# 1_POWER.net
KiCad netlist of a schematic drawn in Altium Designer
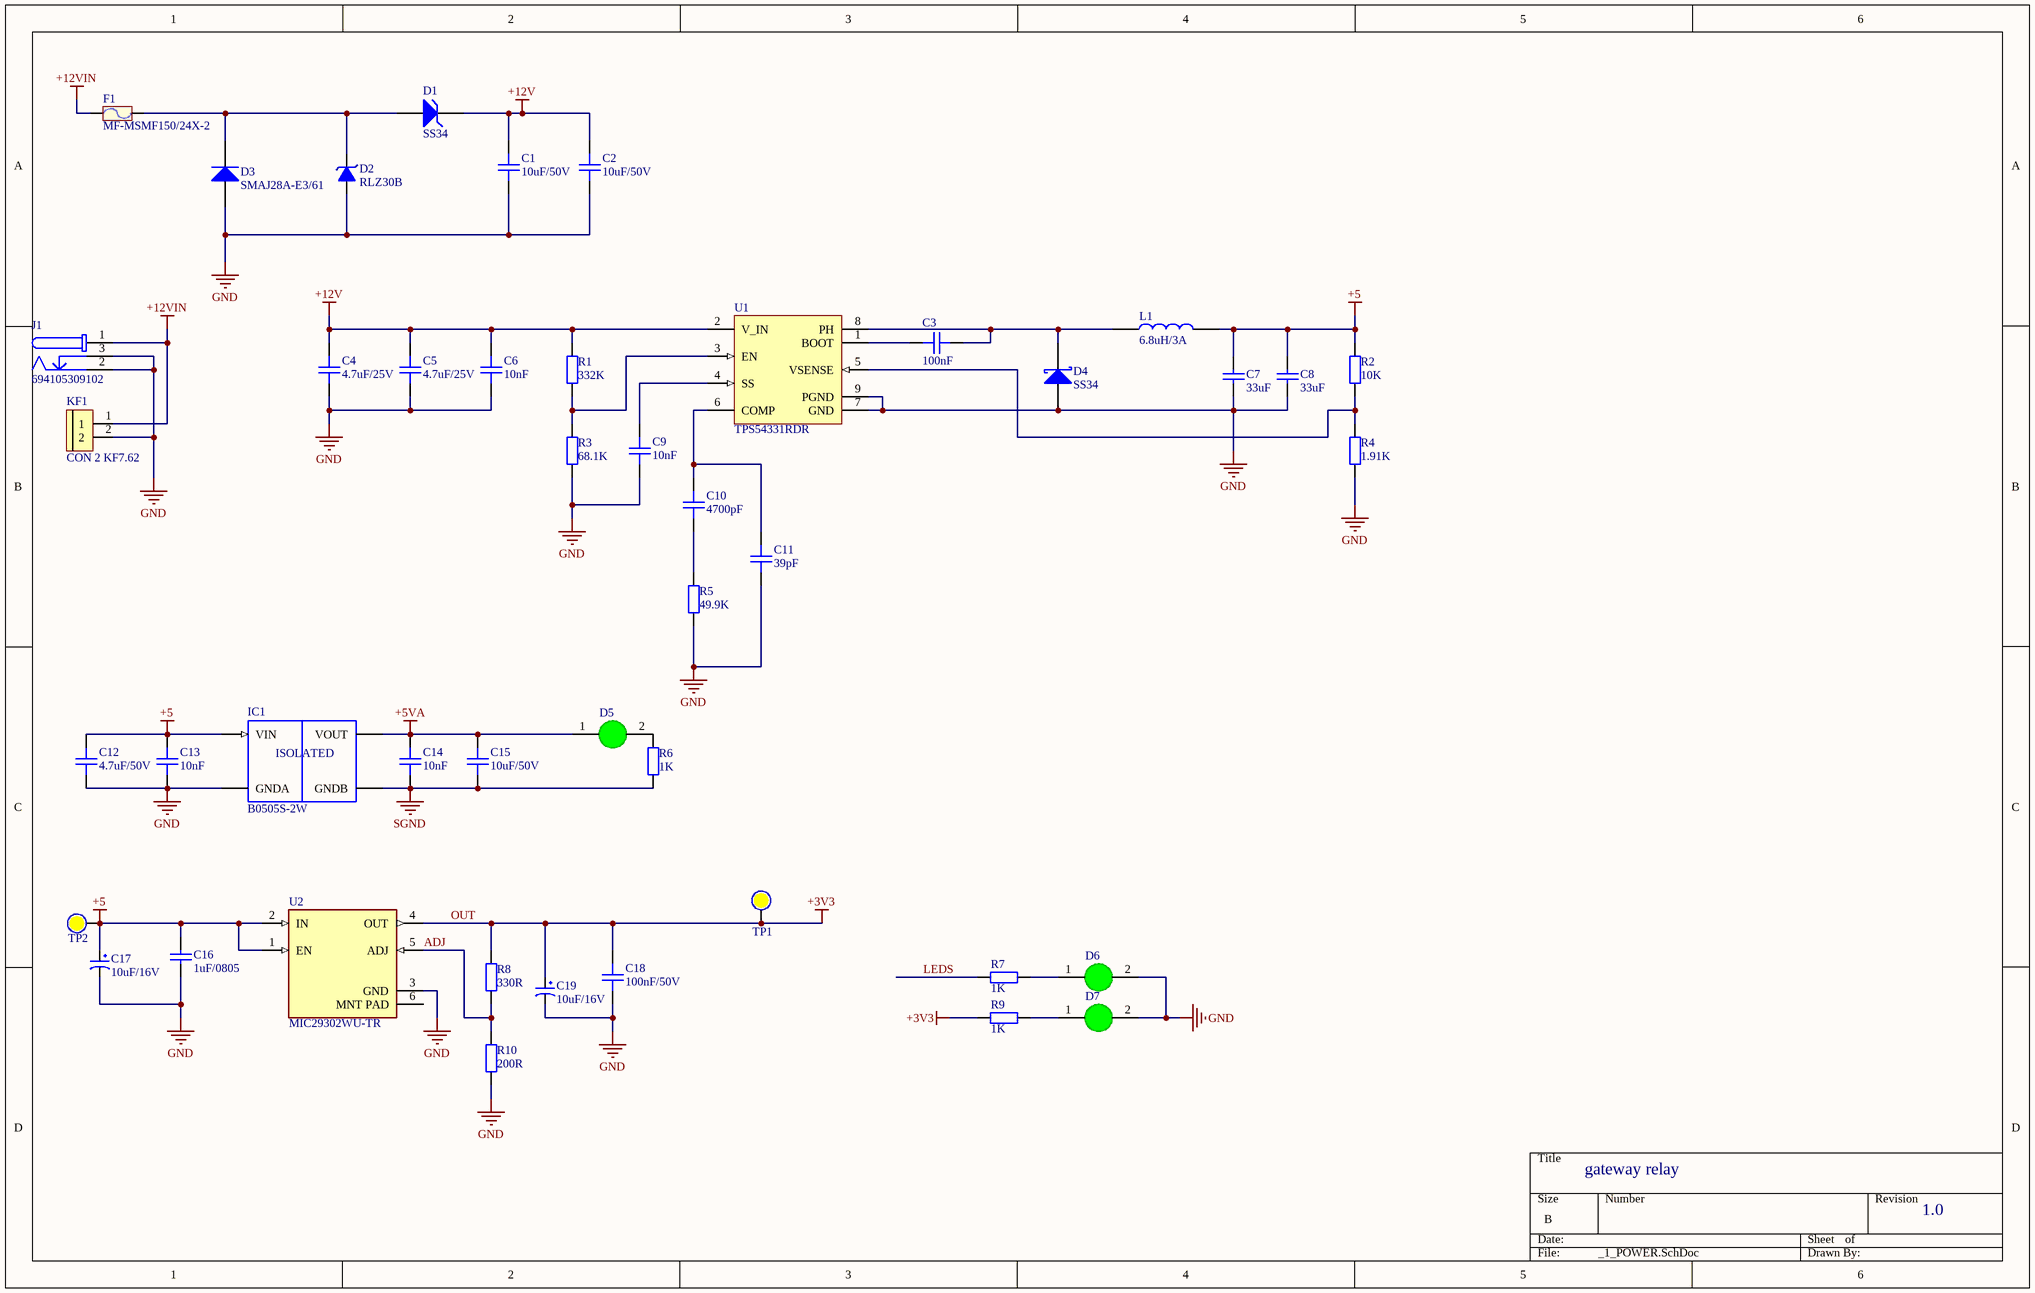
[diagram p0: _1_POWER.SchDoc]

(export (version "E")
  (design (tool "Eeschema 10.0.6"))
  (components
    (comp (ref "C1")
      (value "10uF/50V")
      (footprint "1210")
      (description "CAP CER 10uF/50V 1210")
      (fields (field (name "MANUFACTURER") "Yageo") (field (name "PART NUMBER") "C1210"))
      (libsource (lib "COMPONENT_INS") (part "CAP_CER_1210_10uF"))
    )
    (comp (ref "C2")
      (value "10uF/50V")
      (footprint "1210")
      (description "CAP CER 10uF/50V 1210")
      (fields (field (name "MANUFACTURER") "Yageo") (field (name "PART NUMBER") "C1210"))
      (libsource (lib "COMPONENT_INS") (part "CAP_CER_1210_10uF"))
    )
    (comp (ref "C3")
      (value "100nF")
      (footprint "CAPC-0603 (1608)")
      (description "CAP CER 0.22UF 50V Y5V 0603")
      (fields (field (name "MPN") "CC0603ZRY5V9BB224"))
      (libsource (lib "BYTECH_HW_LIB_2019") (part "CC0603ZRY5V9BB224"))
    )
    (comp (ref "C4")
      (value "4.7uF/25V")
      (footprint "CAPC-1210 (3225)")
      (description "CAP CER 1UF 50V X7R 1210")
      (fields (field (name "MPN") "CC1210KKX7R9BB105") (field (name "MFR") "Yageo"))
      (libsource (lib "BYTECH_HW_LIB_2019") (part "CC1210KKX7R9BB105"))
    )
    (comp (ref "C5")
      (value "4.7uF/25V")
      (footprint "CAPC-1210 (3225)")
      (description "CAP CER 1UF 50V X7R 1210")
      (fields (field (name "MPN") "CC1210KKX7R9BB105") (field (name "MFR") "Yageo"))
      (libsource (lib "BYTECH_HW_LIB_2019") (part "CC1210KKX7R9BB105"))
    )
    (comp (ref "C6")
      (value "10nF")
      (footprint "CAPC-0603 (1608)")
      (description "CAP CER 10nF 16V 10% X7R 0603")
      (fields (field (name "MPN") "CC0603KRX7R7BB103"))
      (libsource (lib "BYTECH_HW_LIB_2019") (part "CC0603KRX7R7BB103"))
    )
    (comp (ref "C7")
      (value "33uF")
      (footprint "tu 1206")
      (description "Dán")
      (libsource (lib "Altium_Lib_by_KhueNguyenCreator") (part "Tu 1206 100pF 50V 5%"))
    )
    (comp (ref "C8")
      (value "33uF")
      (footprint "tu 1206")
      (description "Dán")
      (libsource (lib "Altium_Lib_by_KhueNguyenCreator") (part "Tu 1206 100pF 50V 5%"))
    )
    (comp (ref "C9")
      (value "10nF")
      (footprint "CAPC-0603 (1608)")
      (description "CAP CER 10nF 16V 10% X7R 0603")
      (fields (field (name "MPN") "CC0603KRX7R7BB103"))
      (libsource (lib "BYTECH_HW_LIB_2019") (part "CC0603KRX7R7BB103"))
    )
    (comp (ref "C10")
      (value "4700pF")
      (footprint "CAPC-0603 (1608)")
      (description "CAP CER 8200PF 50V X7R 0603")
      (fields (field (name "MPN") "CC0603KRX7R9BB822") (field (name "MFR") "Yageo"))
      (libsource (lib "BYTECH_HW_LIB_2019") (part "CC0603KRX7R9BB822"))
    )
    (comp (ref "C11")
      (value "39pF")
      (footprint "CAPC-0603 (1608)")
      (description "CAP CER 56PF 50V 5% COG/NPO 0603")
      (fields (field (name "MPN") "CC0603JRNPO9BN560"))
      (libsource (lib "BYTECH_HW_LIB_2019") (part "CC0603JRNPO9BN560"))
    )
    (comp (ref "C12")
      (value "4.7uF/50V")
      (footprint "CAPC-0805 (2012)")
      (description "CAP CER 4.7uF -20% +80% 10V Y5V 0805")
      (fields (field (name "MPN") "CC0805ZRY5V6BB475"))
      (libsource (lib "BYTECH_HW_LIB_2019") (part "CC0805ZRY5V6BB475"))
    )
    (comp (ref "C13")
      (value "10nF")
      (footprint "CAPC-0603 (1608)")
      (description "CAP CER 10nF 16V 10% X7R 0603")
      (fields (field (name "MPN") "CC0603KRX7R7BB103"))
      (libsource (lib "BYTECH_HW_LIB_2019") (part "CC0603KRX7R7BB103"))
    )
    (comp (ref "C14")
      (value "10nF")
      (footprint "CAPC-0603 (1608)")
      (description "CAP CER 10nF 16V 10% X7R 0603")
      (fields (field (name "MPN") "CC0603KRX7R7BB103"))
      (libsource (lib "BYTECH_HW_LIB_2019") (part "CC0603KRX7R7BB103"))
    )
    (comp (ref "C15")
      (value "10uF/50V")
      (footprint "CAPC-0805 (2012)")
      (description "CAP CER 22uF 20% 10V X5R 0805")
      (fields (field (name "MPN") "CC0805MKX5R6BB226"))
      (libsource (lib "BYTECH_HW_LIB_2019") (part "CC0805MKX5R6BB226"))
    )
    (comp (ref "C16")
      (value "1uF/0805")
      (footprint "tu 0805")
      (description "Dán")
      (libsource (lib "Altium_Lib_by_KhueNguyenCreator") (part "Tu 0805 104 50V 10%"))
    )
    (comp (ref "C17")
      (value "10uF/16V")
      (footprint "2312")
      (description "CAP TANT 100uF/10V 2312")
      (fields (field (name "MANUFACTURER") "AVX") (field (name "PART NUMBER") "TAJC107K010RNJ"))
      (libsource (lib "COMPONENT_INS") (part "CAP_TANT_2312_100uF"))
    )
    (comp (ref "C18")
      (value "100nF/50V")
      (footprint "C0805")
      (description "CAP CER 100nF/50V 0805")
      (fields (field (name "MANUFACTURER") "Samsung") (field (name "PART NUMBER") "C0805"))
      (libsource (lib "COMPONENT_INS") (part "CAP_CER_0805_100nF"))
    )
    (comp (ref "C19")
      (value "10uF/16V")
      (footprint "2312")
      (description "CAP TANT 100uF/10V 2312")
      (fields (field (name "MANUFACTURER") "AVX") (field (name "PART NUMBER") "TAJC107K010RNJ"))
      (libsource (lib "COMPONENT_INS") (part "CAP_TANT_2312_100uF"))
    )
    (comp (ref "D1")
      (value "SS34")
      (footprint "DIODE_DO214AA_SMB")
      (description "TVS DIODE 39V  600W SMB")
      (fields (field (name "MPN") "P6SMB39AT3G"))
      (libsource (lib "BYTECH_HW_LIB_2019") (part "P6SMB39AT3G"))
    )
    (comp (ref "D2")
      (value "RLZ30B")
      (footprint "SOD_80")
      (description "ZMM15 15V 500mW SMD SOD-80")
      (fields (field (name "MANUFACTURER") "On Semiconductor") (field (name "PART NUMBER") "ZMM15"))
      (libsource (lib "COMPONENT_INS") (part "DIO_ZMM15"))
    )
    (comp (ref "D3")
      (value "SMAJ28A-E3/61")
      (footprint "VISH-DO-214AC-2_L")
      (fields (field (name "MANUFACTURER") "Vishay Semiconductor"))
      (libsource (lib "Altium Content Vault") (part "VISH-K1A2-2"))
    )
    (comp (ref "D4")
      (value "SS34")
      (footprint "DIODE_DO214AC_SMA")
      (description "DIODE SCHOTTKY 40V 3A SMA")
      (libsource (lib "BYTECH_HW_LIB_2019") (part "SS34"))
    )
    (comp (ref "D5")
      (value "~")
      (footprint "LED_0805_GREEN")
      (description "LED GREEN CLEAR 2V4 20mA 0805 SMD")
      (fields (field (name "MPN") "17-21/G6C-FM1N2B/3T"))
      (libsource (lib "BYTECH_HW_LIB_2019") (part "17-21/G6C-FM1N2B/3T"))
    )
    (comp (ref "D6")
      (value "~")
      (footprint "LED_0805_GREEN")
      (description "LED GREEN CLEAR 2V4 20mA 0805 SMD")
      (fields (field (name "MPN") "17-21/G6C-FM1N2B/3T"))
      (libsource (lib "BYTECH_HW_LIB_2019") (part "17-21/G6C-FM1N2B/3T"))
    )
    (comp (ref "D7")
      (value "~")
      (footprint "LED_0805_GREEN")
      (description "LED GREEN CLEAR 2V4 20mA 0805 SMD")
      (fields (field (name "MPN") "17-21/G6C-FM1N2B/3T"))
      (libsource (lib "BYTECH_HW_LIB_2019") (part "17-21/G6C-FM1N2B/3T"))
    )
    (comp (ref "F1")
      (value "MF-MSMF150/24X-2")
      (footprint "1812")
      (description "MF-MSMF250/16 16V 2.5A1812")
      (fields (field (name "MANUFACTURER") "Bourns") (field (name "PART NUMBER") "1812"))
      (libsource (lib "COMPONENT_INS") (part "FUSE_16V_2.5A"))
    )
    (comp (ref "IC1")
      (value "B0505S-2W")
      (footprint "B0505S-2W")
      (fields (field (name "MF") "MORNSUN"))
      (libsource (lib "B0505S-2W") (part "B0505S-2W"))
    )
    (comp (ref "J1")
      (value "694105309102")
      (footprint "PCBComponent_1")
      (libsource (lib "DC-091") (part "CMP-1502-00187-2"))
    )
    (comp (ref "KF1")
      (value "CON 2 KF7.62")
      (footprint "CON 2 KF7.62")
      (description "Cắm")
      (libsource (lib "Altium_Lib_by_KhueNguyenCreator") (part "CON 2 KF7.62"))
    )
    (comp (ref "L1")
      (value "6.8uH/3A")
      (footprint "Cuon Cam 12x12x10")
      (description "Dán")
      (libsource (lib "Altium_Lib_by_KhueNguyenCreator") (part "CUON CAM 100uH SMD"))
    )
    (comp (ref "R1")
      (value "332K")
      (footprint "RESC-0603 (1608)")
      (description "RES SMD 330K OHM 1% 1/10W 0603")
      (fields (field (name "MPN") "RC0603FR-07330KL"))
      (libsource (lib "BYTECH_HW_LIB_2019") (part "RC0603FR-07330KL"))
    )
    (comp (ref "R2")
      (value "10K")
      (footprint "RESC-0805 (2012)")
      (description "RES SMD 10K OHM 1% 1/8W 0805")
      (fields (field (name "MPN") "RC0805FR-0710KL"))
      (libsource (lib "BYTECH_HW_LIB_2019") (part "RC0805FR-0710KL"))
    )
    (comp (ref "R3")
      (value "68.1K")
      (footprint "RESC-0603 (1608)")
      (description "RES SMD 68K OHM 1% 1/10W 0603")
      (fields (field (name "MPN") "RC0603FR-0768KL"))
      (libsource (lib "BYTECH_HW_LIB_2019") (part "RC0603FR-0768KL"))
    )
    (comp (ref "R4")
      (value "1.91K")
      (footprint "RESC-0805 (2012)")
      (description "RES SMD 1.1K OHM 1% 1/8W 0805")
      (fields (field (name "MPN") "RC0805FR-071K1L"))
      (libsource (lib "BYTECH_HW_LIB_2019") (part "RC0805FR-071K1L"))
    )
    (comp (ref "R5")
      (value "49.9K")
      (footprint "RESC-0603 (1608)")
      (description "RES SMD 47K OHM 1% 1/10W 0603")
      (fields (field (name "MPN") "RC0603FR0747KL"))
      (libsource (lib "BYTECH_HW_LIB_2019") (part "RC0603FR0747KL"))
    )
    (comp (ref "R6")
      (value "1K")
      (footprint "RESC-0805 (2012)")
      (description "RES SMD 1K OHM 1% 1/8W 0805")
      (fields (field (name "MPN") "RC0805FR-071KL"))
      (libsource (lib "BYTECH_HW_LIB_2019") (part "RC0805FR-071KL"))
    )
    (comp (ref "R7")
      (value "1K")
      (footprint "RESC-0805 (2012)")
      (description "RES SMD 1K OHM 1% 1/8W 0805")
      (fields (field (name "MPN") "RC0805FR-071KL"))
      (libsource (lib "") (part "RC0805FR-071KL_1"))
    )
    (comp (ref "R8")
      (value "330R")
      (footprint "RESC-0805 (2012)")
      (description "RES SMD 330 OHM 1% 1/8W 0805")
      (fields (field (name "MPN") "RC0805FR-07330RL"))
      (libsource (lib "BYTECH_HW_LIB_2019") (part "RC0805FR-07330RL"))
    )
    (comp (ref "R9")
      (value "1K")
      (footprint "RESC-0805 (2012)")
      (description "RES SMD 1K OHM 1% 1/8W 0805")
      (fields (field (name "MPN") "RC0805FR-071KL"))
      (libsource (lib "") (part "RC0805FR-071KL_1"))
    )
    (comp (ref "R10")
      (value "200R")
      (footprint "RESC-0805 (2012)")
      (description "RES SMD 300 OHM 1% 1/8W 0805")
      (fields (field (name "MPN") "RC0805FR-07300RL"))
      (libsource (lib "BYTECH_HW_LIB_2019") (part "RC0805FR-07300RL"))
    )
    (comp (ref "TP1")
      (value "~")
      (footprint "Test Point 1 MM")
      (description "Test Point")
      (libsource (lib "BYTECH_HW_LIB_2019") (part "Test Point"))
    )
    (comp (ref "TP2")
      (value "~")
      (footprint "Test Point 1 MM")
      (description "Test Point")
      (libsource (lib "") (part "Test Point_1"))
    )
    (comp (ref "U1")
      (value "TPS54331RDR")
      (footprint "SOIC-8-TP")
      (description "Step Down DC-DC Converter")
      (fields (field (name "MPN") "TPS54360DDAR"))
      (libsource (lib "BYTECH_HW_LIB_2019") (part "TPS54360DDAR"))
    )
    (comp (ref "U2")
      (value "MIC29302WU-TR")
      (footprint "FP-C04-012-MFG")
      (description "IC REG LINEAR POS ADJ 3A TO263-5")
      (fields
        (field (name "MANUFACTURER") "Microchip")
        (field (name "OCTOPART") "https://octopart.com/mic29302wu-tr-microchip-66801318")
      )
      (libsource (lib "Altium Content Vault") (part "0db40f55fda0e91d0d14528974a446d"))
    )
  )
  (nets
    (net (code "1") (name "+3V3") (class "Default")
      (node (ref "C18") (pin "2") (pinfunction "2_2") (pintype "passive"))
      (node (ref "C19") (pin "1") (pinfunction "1_1") (pintype "passive"))
      (node (ref "R8") (pin "2") (pinfunction "2_2") (pintype "passive"))
      (node (ref "R9") (pin "1") (pinfunction "1_1") (pintype "passive"))
      (node (ref "TP1") (pin "0") (pinfunction "0_0") (pintype "passive"))
      (node (ref "U2") (pin "4") (pinfunction "OUT_4") (pintype "output"))
    )
    (net (code "2") (name "+5") (class "Default")
      (node (ref "C12") (pin "2") (pinfunction "2_2") (pintype "passive"))
      (node (ref "C13") (pin "2") (pinfunction "2_2") (pintype "passive"))
      (node (ref "C16") (pin "1") (pinfunction "1_1") (pintype "passive"))
      (node (ref "C17") (pin "1") (pinfunction "1_1") (pintype "passive"))
      (node (ref "C7") (pin "1") (pinfunction "1_1") (pintype "passive"))
      (node (ref "C8") (pin "1") (pinfunction "1_1") (pintype "passive"))
      (node (ref "IC1") (pin "VIN") (pinfunction "VIN_VIN") (pintype "input"))
      (node (ref "L1") (pin "2") (pinfunction "2_2") (pintype "passive"))
      (node (ref "R2") (pin "2") (pinfunction "2_2") (pintype "passive"))
      (node (ref "TP2") (pin "0") (pinfunction "0_0") (pintype "passive"))
      (node (ref "U2") (pin "1") (pinfunction "EN_1") (pintype "input"))
      (node (ref "U2") (pin "2") (pinfunction "IN_2") (pintype "input"))
    )
    (net (code "3") (name "+5VA") (class "Default")
      (node (ref "C14") (pin "2") (pinfunction "2_2") (pintype "passive"))
      (node (ref "C15") (pin "2") (pinfunction "2_2") (pintype "passive"))
      (node (ref "D5") (pin "1") (pinfunction "A_1") (pintype "passive"))
      (node (ref "IC1") (pin "VOUT") (pinfunction "VOUT_VOUT") (pintype "power_in"))
    )
    (net (code "4") (name "+12V") (class "Default")
      (node (ref "C1") (pin "2") (pinfunction "2_2") (pintype "passive"))
      (node (ref "C2") (pin "2") (pinfunction "2_2") (pintype "passive"))
      (node (ref "C4") (pin "2") (pinfunction "2_2") (pintype "passive"))
      (node (ref "C5") (pin "2") (pinfunction "2_2") (pintype "passive"))
      (node (ref "C6") (pin "2") (pinfunction "2_2") (pintype "passive"))
      (node (ref "D1") (pin "2") (pinfunction "K_2") (pintype "passive"))
      (node (ref "R1") (pin "2") (pinfunction "2_2") (pintype "passive"))
      (node (ref "U1") (pin "2") (pinfunction "V_IN_2") (pintype "passive"))
    )
    (net (code "5") (name "+12VIN") (class "Default")
      (node (ref "F1") (pin "1") (pinfunction "1_1") (pintype "passive"))
      (node (ref "J1") (pin "1") (pinfunction "1_1") (pintype "passive"))
      (node (ref "KF1") (pin "1") (pinfunction "1_1") (pintype "passive"))
    )
    (net (code "6") (name "/ADJ") (class "Default")
      (node (ref "R10") (pin "2") (pinfunction "2_2") (pintype "passive"))
      (node (ref "R8") (pin "1") (pinfunction "1_1") (pintype "passive"))
      (node (ref "U2") (pin "5") (pinfunction "ADJ_5") (pintype "input"))
    )
    (net (code "7") (name "/LEDS") (class "Default")
      (node (ref "R7") (pin "1") (pinfunction "1_1") (pintype "passive"))
    )
    (net (code "8") (name "GND") (class "Default")
      (node (ref "C1") (pin "1") (pinfunction "1_1") (pintype "passive"))
      (node (ref "C11") (pin "1") (pinfunction "1_1") (pintype "passive"))
      (node (ref "C12") (pin "1") (pinfunction "1_1") (pintype "passive"))
      (node (ref "C13") (pin "1") (pinfunction "1_1") (pintype "passive"))
      (node (ref "C16") (pin "2") (pinfunction "2_2") (pintype "passive"))
      (node (ref "C17") (pin "2") (pinfunction "2_2") (pintype "passive"))
      (node (ref "C18") (pin "1") (pinfunction "1_1") (pintype "passive"))
      (node (ref "C19") (pin "2") (pinfunction "2_2") (pintype "passive"))
      (node (ref "C2") (pin "1") (pinfunction "1_1") (pintype "passive"))
      (node (ref "C4") (pin "1") (pinfunction "1_1") (pintype "passive"))
      (node (ref "C5") (pin "1") (pinfunction "1_1") (pintype "passive"))
      (node (ref "C6") (pin "1") (pinfunction "1_1") (pintype "passive"))
      (node (ref "C7") (pin "2") (pinfunction "2_2") (pintype "passive"))
      (node (ref "C8") (pin "2") (pinfunction "2_2") (pintype "passive"))
      (node (ref "C9") (pin "1") (pinfunction "1_1") (pintype "passive"))
      (node (ref "D2") (pin "1") (pinfunction "A_1") (pintype "passive"))
      (node (ref "D3") (pin "2") (pinfunction "A_2") (pintype "passive"))
      (node (ref "D4") (pin "1") (pinfunction "A_1") (pintype "passive"))
      (node (ref "D6") (pin "2") (pinfunction "K_2") (pintype "passive"))
      (node (ref "D7") (pin "2") (pinfunction "K_2") (pintype "passive"))
      (node (ref "IC1") (pin "GNDA") (pinfunction "GNDA_GNDA") (pintype "power_in"))
      (node (ref "J1") (pin "2") (pinfunction "2_2") (pintype "passive"))
      (node (ref "J1") (pin "3") (pinfunction "3_3") (pintype "passive"))
      (node (ref "KF1") (pin "2") (pinfunction "2_2") (pintype "passive"))
      (node (ref "R10") (pin "1") (pinfunction "1_1") (pintype "passive"))
      (node (ref "R3") (pin "1") (pinfunction "1_1") (pintype "passive"))
      (node (ref "R4") (pin "1") (pinfunction "1_1") (pintype "passive"))
      (node (ref "R5") (pin "1") (pinfunction "1_1") (pintype "passive"))
      (node (ref "U1") (pin "7") (pinfunction "GND_7") (pintype "passive"))
      (node (ref "U1") (pin "9") (pinfunction "PGND_9") (pintype "passive"))
      (node (ref "U2") (pin "3") (pinfunction "GND_3") (pintype "power_in"))
    )
    (net (code "9") (name "Net-(C10-Pad1)") (class "Default")
      (node (ref "C10") (pin "1") (pinfunction "1_1") (pintype "passive"))
      (node (ref "R5") (pin "2") (pinfunction "2_2") (pintype "passive"))
    )
    (net (code "10") (name "Net-(D1-A)") (class "Default")
      (node (ref "D1") (pin "1") (pinfunction "A_1") (pintype "passive"))
      (node (ref "D2") (pin "2") (pinfunction "K_2") (pintype "passive"))
      (node (ref "D3") (pin "1") (pinfunction "K_1") (pintype "passive"))
      (node (ref "F1") (pin "2") (pinfunction "2_2") (pintype "passive"))
    )
    (net (code "11") (name "Net-(D4-K)") (class "Default")
      (node (ref "C3") (pin "2") (pinfunction "2_2") (pintype "passive"))
      (node (ref "D4") (pin "2") (pinfunction "K_2") (pintype "passive"))
      (node (ref "L1") (pin "1") (pinfunction "1_1") (pintype "passive"))
      (node (ref "U1") (pin "8") (pinfunction "PH_8") (pintype "passive"))
    )
    (net (code "12") (name "Net-(D5-K)") (class "Default")
      (node (ref "D5") (pin "2") (pinfunction "K_2") (pintype "passive"))
      (node (ref "R6") (pin "1") (pinfunction "1_1") (pintype "passive"))
    )
    (net (code "13") (name "Net-(D6-A)") (class "Default")
      (node (ref "D6") (pin "1") (pinfunction "A_1") (pintype "passive"))
      (node (ref "R7") (pin "2") (pinfunction "2_2") (pintype "passive"))
    )
    (net (code "14") (name "Net-(D7-A)") (class "Default")
      (node (ref "D7") (pin "1") (pinfunction "A_1") (pintype "passive"))
      (node (ref "R9") (pin "2") (pinfunction "2_2") (pintype "passive"))
    )
    (net (code "15") (name "Net-(U1-BOOT)") (class "Default")
      (node (ref "C3") (pin "1") (pinfunction "1_1") (pintype "passive"))
      (node (ref "U1") (pin "1") (pinfunction "BOOT_1") (pintype "passive"))
    )
    (net (code "16") (name "Net-(U1-COMP)") (class "Default")
      (node (ref "C10") (pin "2") (pinfunction "2_2") (pintype "passive"))
      (node (ref "C11") (pin "2") (pinfunction "2_2") (pintype "passive"))
      (node (ref "U1") (pin "6") (pinfunction "COMP_6") (pintype "passive"))
    )
    (net (code "17") (name "Net-(U1-EN)") (class "Default")
      (node (ref "R1") (pin "1") (pinfunction "1_1") (pintype "passive"))
      (node (ref "R3") (pin "2") (pinfunction "2_2") (pintype "passive"))
      (node (ref "U1") (pin "3") (pinfunction "EN_3") (pintype "input"))
    )
    (net (code "18") (name "Net-(U1-SS)") (class "Default")
      (node (ref "C9") (pin "2") (pinfunction "2_2") (pintype "passive"))
      (node (ref "U1") (pin "4") (pinfunction "SS_4") (pintype "input"))
    )
    (net (code "19") (name "Net-(U1-VSENSE)") (class "Default")
      (node (ref "R2") (pin "1") (pinfunction "1_1") (pintype "passive"))
      (node (ref "R4") (pin "2") (pinfunction "2_2") (pintype "passive"))
      (node (ref "U1") (pin "5") (pinfunction "VSENSE_5") (pintype "input"))
    )
    (net (code "20") (name "PGND") (class "Default")
      (node (ref "U1") (pin "9") (pinfunction "TP_9") (pintype "passive"))
    )
    (net (code "21") (name "SGND") (class "Default")
      (node (ref "C14") (pin "1") (pinfunction "1_1") (pintype "passive"))
      (node (ref "C15") (pin "1") (pinfunction "1_1") (pintype "passive"))
      (node (ref "IC1") (pin "GNDB") (pinfunction "GNDB_GNDB") (pintype "power_in"))
      (node (ref "R6") (pin "2") (pinfunction "2_2") (pintype "passive"))
    )
    (net (code "22") (name "unconnected-(U2-MNT_PAD-Pad6)") (class "Default")
      (node (ref "U2") (pin "6") (pinfunction "MNT_PAD_6") (pintype "passive"))
    )
  )
)
